# LM334.net
KiCad netlist of a schematic drawn in Altium Designer
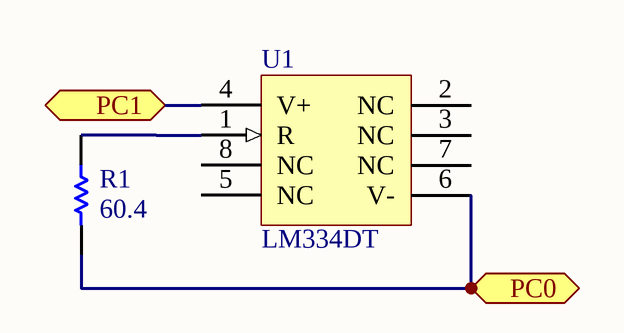
[diagram p0: LM334.SchDoc]

(export (version "E")
  (design (tool "Eeschema 10.0.6"))
  (components
    (comp (ref "R1")
      (value "60.4")
      (footprint "SMD-0805-RES")
      (description "Resistor")
      (fields (field (name "Comment") "Res1") (field (name "PUBLISHER") "Altium Limited"))
      (libsource (lib "Schlib1") (part "Res1"))
    )
    (comp (ref "U1")
      (value "LM334DT")
      (footprint "M08A_M")
      (description "3-Terminal Adjustable Current Source, 8-pin Narrow SOIC")
      (fields (field (name "PARTNUMBER") "LM334M") (field (name "MANUFACTURER") "National Semiconductor"))
      (libsource (lib "Tesis") (part "LM334DT"))
    )
  )
  (nets
    (net (code "1") (name "/PC0") (class "Default")
      (node (ref "R1") (pin "2") (pinfunction "2_2") (pintype "passive"))
      (node (ref "U1") (pin "6") (pinfunction "V-_6") (pintype "passive"))
    )
    (net (code "2") (name "/PC1") (class "Default")
      (node (ref "U1") (pin "4") (pinfunction "V+_4") (pintype "passive"))
    )
    (net (code "3") (name "Net-(U1-R)") (class "Default")
      (node (ref "R1") (pin "1") (pinfunction "1_1") (pintype "passive"))
      (node (ref "U1") (pin "1") (pinfunction "R_1") (pintype "input"))
    )
    (net (code "4") (name "unconnected-(U1-NC-Pad2)") (class "Default")
      (node (ref "U1") (pin "2") (pinfunction "NC_2") (pintype "passive"))
    )
    (net (code "5") (name "unconnected-(U1-NC-Pad3)") (class "Default")
      (node (ref "U1") (pin "3") (pinfunction "NC_3") (pintype "passive"))
    )
    (net (code "6") (name "unconnected-(U1-NC-Pad5)") (class "Default")
      (node (ref "U1") (pin "5") (pinfunction "NC_5") (pintype "passive"))
    )
    (net (code "7") (name "unconnected-(U1-NC-Pad7)") (class "Default")
      (node (ref "U1") (pin "7") (pinfunction "NC_7") (pintype "passive"))
    )
    (net (code "8") (name "unconnected-(U1-NC-Pad8)") (class "Default")
      (node (ref "U1") (pin "8") (pinfunction "NC_8") (pintype "passive"))
    )
  )
)
